# SNES-1Chip_MR_QID.net
KiCad netlist of a schematic drawn in EAGLE
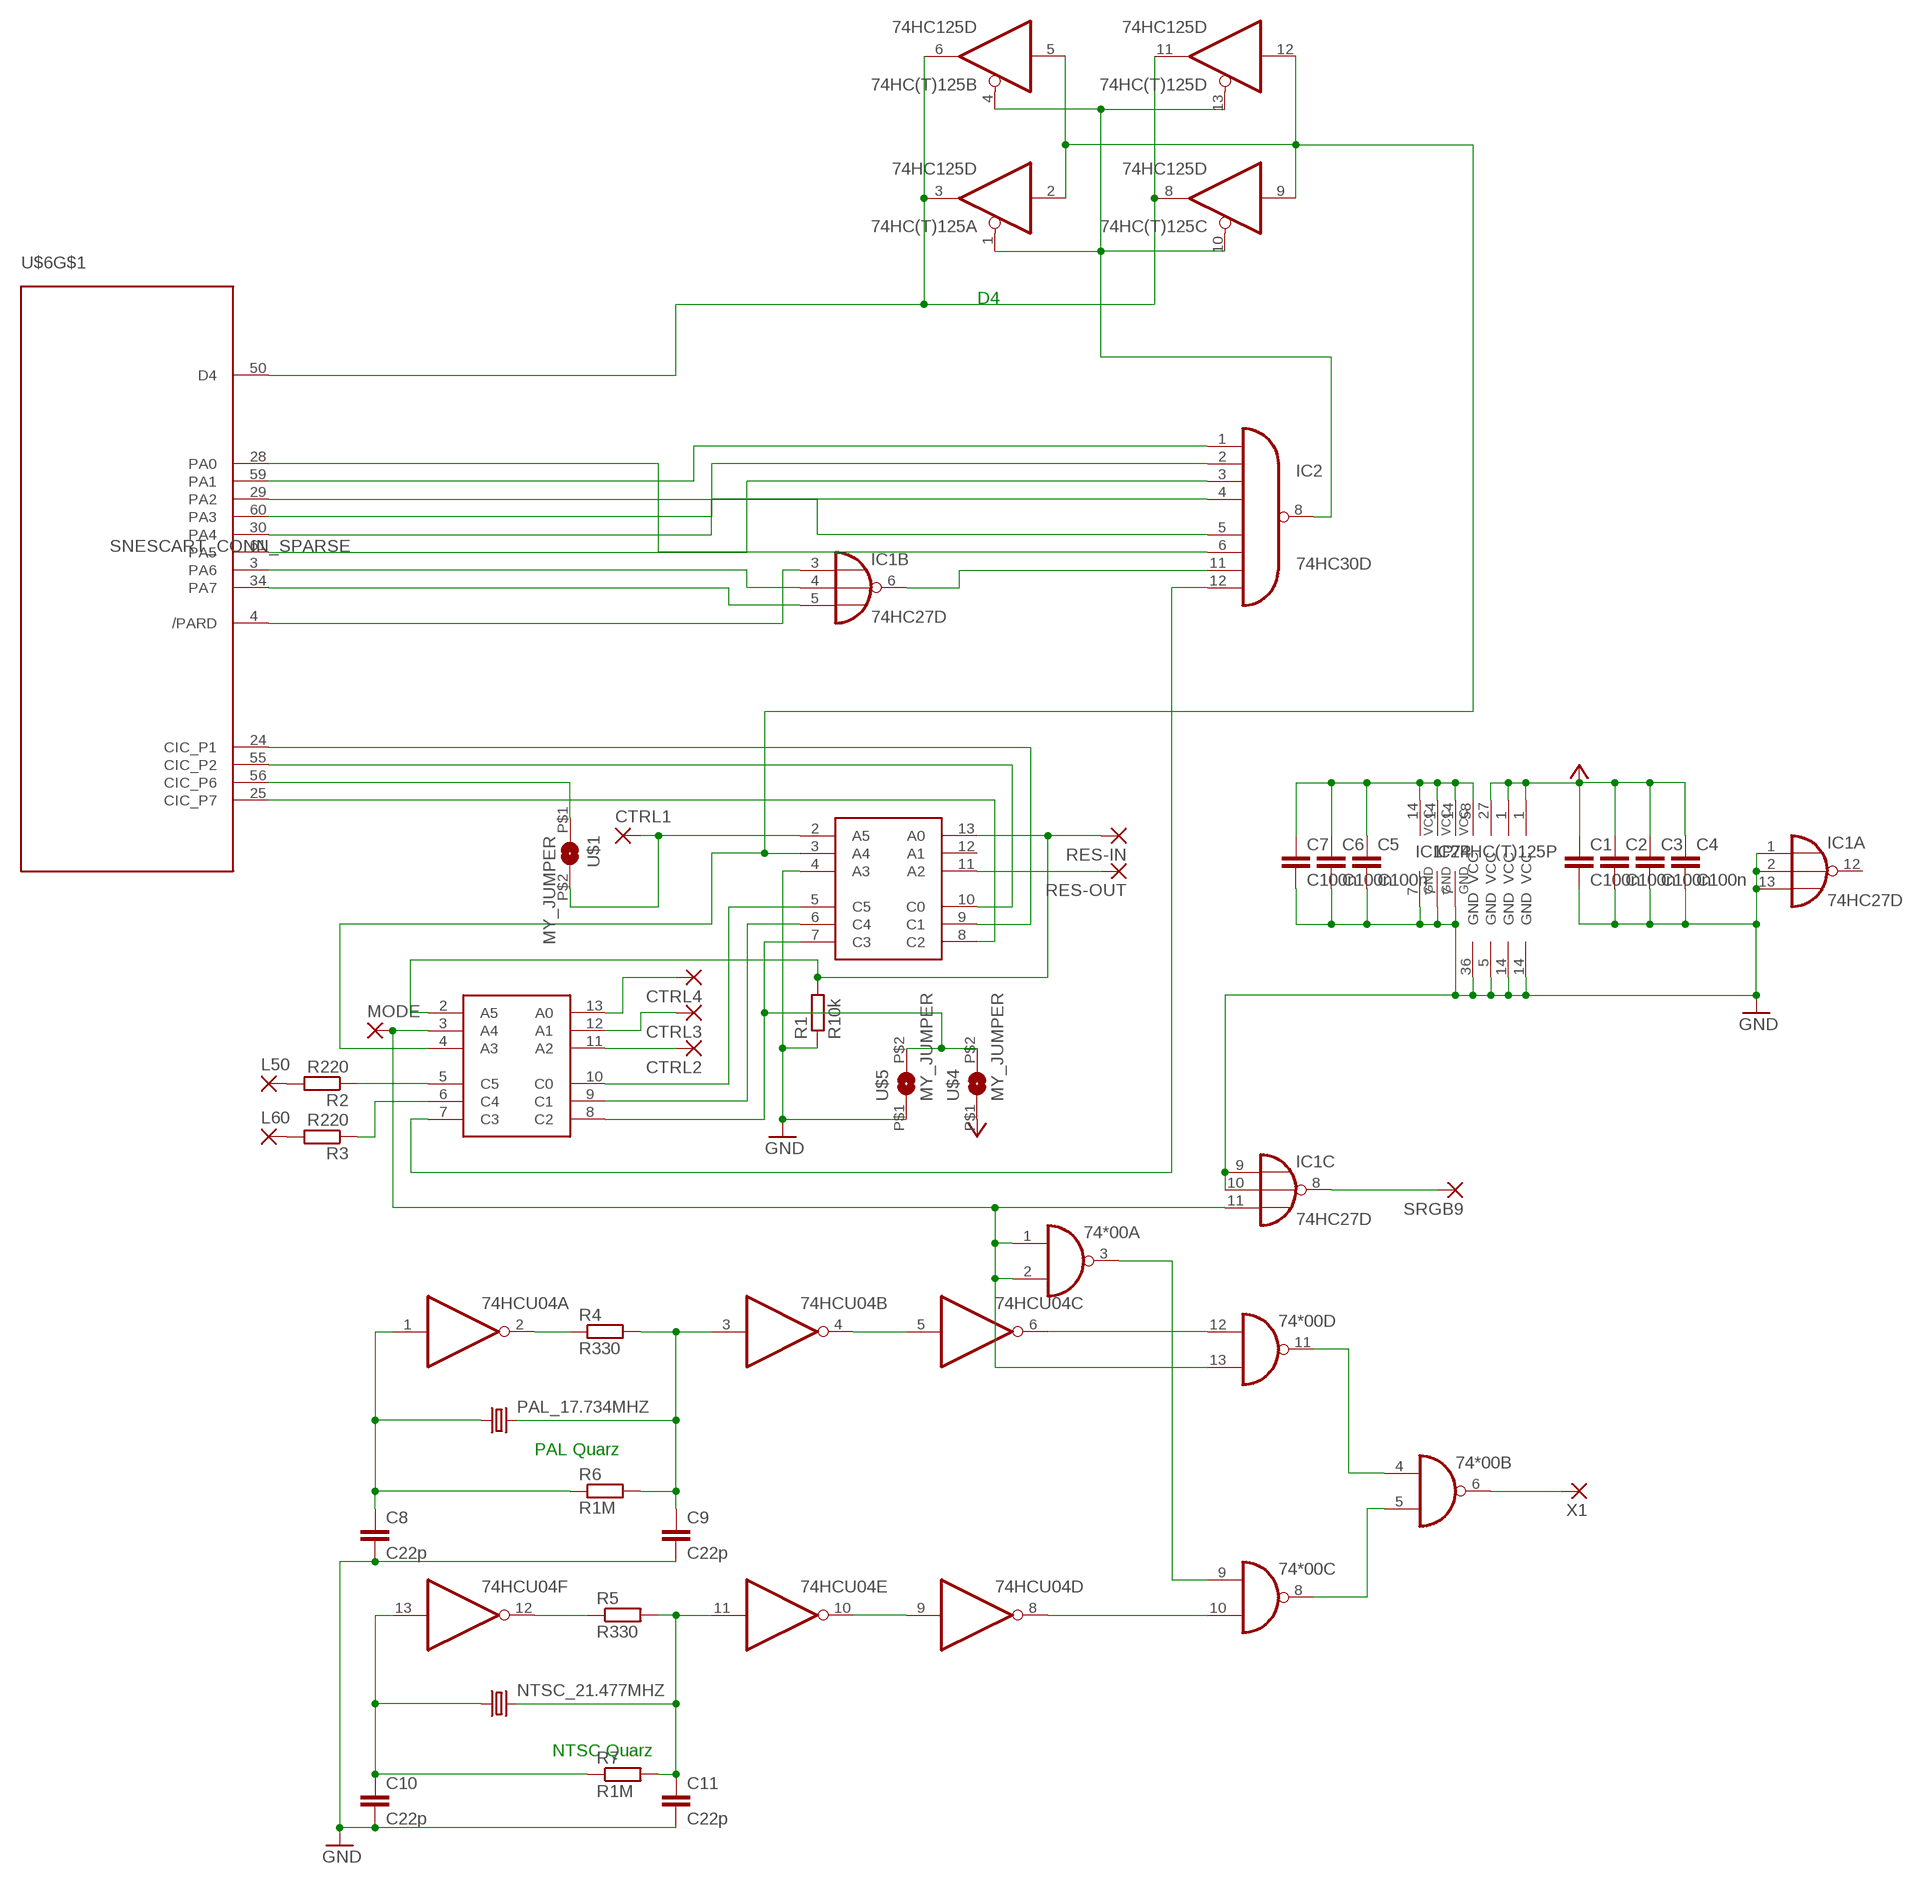
[diagram p0: schematic, sheet 1]

(export (version "E")
  (design (tool "Eeschema 10.0.6"))
  (components
    (comp (ref "74*00")
      (value "7400D")
      (footprint "eagle-import:SO14")
      (libsource (lib "eagle-import") (part "7400D"))
    )
    (comp (ref "74HC(T)125")
      (value "74HC125D")
      (footprint "eagle-import:SO14")
      (libsource (lib "eagle-import") (part "74125DHC"))
    )
    (comp (ref "74HCU04")
      (value "74HC04D")
      (footprint "eagle-import:SO14")
      (libsource (lib "eagle-import") (part "7404DHC"))
    )
    (comp (ref "C1")
      (value "C100n")
      (footprint "eagle-import:Z0805")
      (libsource (lib "eagle-import") (part "C0805"))
    )
    (comp (ref "C2")
      (value "C100n")
      (footprint "eagle-import:Z0805")
      (libsource (lib "eagle-import") (part "C0805"))
    )
    (comp (ref "C3")
      (value "C100n")
      (footprint "eagle-import:Z0805")
      (libsource (lib "eagle-import") (part "C0805"))
    )
    (comp (ref "C4")
      (value "C100n")
      (footprint "eagle-import:Z0805")
      (libsource (lib "eagle-import") (part "C0805"))
    )
    (comp (ref "C5")
      (value "C100n")
      (footprint "eagle-import:Z0805")
      (libsource (lib "eagle-import") (part "C0805"))
    )
    (comp (ref "C6")
      (value "C100n")
      (footprint "eagle-import:Z0805")
      (libsource (lib "eagle-import") (part "C0805"))
    )
    (comp (ref "C7")
      (value "C100n")
      (footprint "eagle-import:Z0805")
      (libsource (lib "eagle-import") (part "C0805"))
    )
    (comp (ref "C8")
      (value "C22p")
      (footprint "eagle-import:Z0805")
      (libsource (lib "eagle-import") (part "C0805"))
    )
    (comp (ref "C9")
      (value "C22p")
      (footprint "eagle-import:Z0805")
      (libsource (lib "eagle-import") (part "C0805"))
    )
    (comp (ref "C10")
      (value "C22p")
      (footprint "eagle-import:Z0805")
      (libsource (lib "eagle-import") (part "C0805"))
    )
    (comp (ref "C11")
      (value "C22p")
      (footprint "eagle-import:Z0805")
      (libsource (lib "eagle-import") (part "C0805"))
    )
    (comp (ref "CTRL1")
      (value "SMD2")
      (footprint "eagle-import:SMD1,27-2,54")
      (libsource (lib "eagle-import") (part "SMD2"))
    )
    (comp (ref "CTRL2")
      (value "SMD2")
      (footprint "eagle-import:SMD1,27-2,54")
      (libsource (lib "eagle-import") (part "SMD2"))
    )
    (comp (ref "CTRL3")
      (value "SMD2")
      (footprint "eagle-import:SMD1,27-2,54")
      (libsource (lib "eagle-import") (part "SMD2"))
    )
    (comp (ref "CTRL4")
      (value "SMD2")
      (footprint "eagle-import:SMD1,27-2,54")
      (libsource (lib "eagle-import") (part "SMD2"))
    )
    (comp (ref "IC1")
      (value "74HC27D")
      (footprint "eagle-import:SO14")
      (libsource (lib "eagle-import") (part "7427DHC"))
    )
    (comp (ref "IC2")
      (value "74HC30D")
      (footprint "eagle-import:SO14")
      (libsource (lib "eagle-import") (part "7430DHC"))
    )
    (comp (ref "L50")
      (value "SMD2")
      (footprint "eagle-import:SMD1,27-2,54")
      (libsource (lib "eagle-import") (part "SMD2"))
    )
    (comp (ref "L60")
      (value "SMD2")
      (footprint "eagle-import:SMD1,27-2,54")
      (libsource (lib "eagle-import") (part "SMD2"))
    )
    (comp (ref "MODE")
      (value "SMD2")
      (footprint "eagle-import:SMD1,27-2,54")
      (libsource (lib "eagle-import") (part "SMD2"))
    )
    (comp (ref "NTSC_21.477MHZ")
      (value "CRYSTALHC49UP")
      (footprint "eagle-import:HC49UP")
      (libsource (lib "eagle-import") (part "CRYSTALHC49UP"))
    )
    (comp (ref "PAL_17.734MHZ")
      (value "CRYSTALHC49UP")
      (footprint "eagle-import:HC49UP")
      (libsource (lib "eagle-import") (part "CRYSTALHC49UP"))
    )
    (comp (ref "R1")
      (value "R10k")
      (footprint "eagle-import:Z0805")
      (libsource (lib "eagle-import") (part "R0805"))
    )
    (comp (ref "R2")
      (value "R220")
      (footprint "eagle-import:Z0805")
      (libsource (lib "eagle-import") (part "R0805"))
    )
    (comp (ref "R3")
      (value "R220")
      (footprint "eagle-import:Z0805")
      (libsource (lib "eagle-import") (part "R0805"))
    )
    (comp (ref "R4")
      (value "R330")
      (footprint "eagle-import:Z0805")
      (libsource (lib "eagle-import") (part "R0805"))
    )
    (comp (ref "R5")
      (value "R330")
      (footprint "eagle-import:Z0805")
      (libsource (lib "eagle-import") (part "R0805"))
    )
    (comp (ref "R6")
      (value "R1M")
      (footprint "eagle-import:Z0805")
      (libsource (lib "eagle-import") (part "R0805"))
    )
    (comp (ref "R7")
      (value "R1M")
      (footprint "eagle-import:Z0805")
      (libsource (lib "eagle-import") (part "R0805"))
    )
    (comp (ref "RES-IN")
      (value "SMD2")
      (footprint "eagle-import:SMD1,27-2,54")
      (libsource (lib "eagle-import") (part "SMD2"))
    )
    (comp (ref "RES-OUT")
      (value "SMD2")
      (footprint "eagle-import:SMD1,27-2,54")
      (libsource (lib "eagle-import") (part "SMD2"))
    )
    (comp (ref "SRGB9")
      (value "SMD2")
      (footprint "eagle-import:SMD1,27-2,54")
      (libsource (lib "eagle-import") (part "SMD2"))
    )
    (comp (ref "U$1")
      (value "MY_JUMPER")
      (footprint "eagle-import:MYJUMP")
      (libsource (lib "eagle-import") (part "MY_JUMPER"))
    )
    (comp (ref "U$2")
      (value "PIC16F630_SIMPLE")
      (footprint "eagle-import:PIC16F630")
      (libsource (lib "eagle-import") (part "PIC16F630_SIMPLE"))
    )
    (comp (ref "U$3")
      (value "PIC16F630_SIMPLE")
      (footprint "eagle-import:PIC16F630")
      (libsource (lib "eagle-import") (part "PIC16F630_SIMPLE"))
    )
    (comp (ref "U$4")
      (value "MY_JUMPER")
      (footprint "eagle-import:MYJUMP")
      (libsource (lib "eagle-import") (part "MY_JUMPER"))
    )
    (comp (ref "U$5")
      (value "MY_JUMPER")
      (footprint "eagle-import:MYJUMP")
      (libsource (lib "eagle-import") (part "MY_JUMPER"))
    )
    (comp (ref "U$6")
      (value "SNESCART_CONN_SPARSE")
      (footprint "eagle-import:SNESCART_CONN_SPARSE")
      (libsource (lib "eagle-import") (part "SNESCART_CONN_SPARSE"))
    )
    (comp (ref "X1")
      (value "SMD2")
      (footprint "eagle-import:SMD1,27-2,54")
      (libsource (lib "eagle-import") (part "SMD2"))
    )
  )
  (nets
    (net (code "1") (name "+5V") (class "Default")
      (node (ref "C1") (pin "1") (pinfunction "1_1") (pintype "passive"))
      (node (ref "C2") (pin "1") (pinfunction "1_1") (pintype "passive"))
      (node (ref "C3") (pin "1") (pinfunction "1_1") (pintype "passive"))
      (node (ref "C4") (pin "1") (pinfunction "1_1") (pintype "passive"))
      (node (ref "U$2") (pin "1") (pinfunction "VCC_1") (pintype "bidirectional"))
      (node (ref "U$3") (pin "1") (pinfunction "VCC_1") (pintype "bidirectional"))
      (node (ref "U$4") (pin "P$1") (pinfunction "1_P$1") (pintype "passive"))
      (node (ref "U$6") (pin "27") (pinfunction "VCC_27") (pintype "bidirectional"))
    )
    (net (code "2") (name "GND") (class "Default")
      (node (ref "74HC(T)125") (pin "7") (pinfunction "GND_7") (pintype "power_in"))
      (node (ref "C1") (pin "2") (pinfunction "2_2") (pintype "passive"))
      (node (ref "C10") (pin "2") (pinfunction "2_2") (pintype "passive"))
      (node (ref "C11") (pin "2") (pinfunction "2_2") (pintype "passive"))
      (node (ref "C2") (pin "2") (pinfunction "2_2") (pintype "passive"))
      (node (ref "C3") (pin "2") (pinfunction "2_2") (pintype "passive"))
      (node (ref "C4") (pin "2") (pinfunction "2_2") (pintype "passive"))
      (node (ref "C5") (pin "2") (pinfunction "2_2") (pintype "passive"))
      (node (ref "C6") (pin "2") (pinfunction "2_2") (pintype "passive"))
      (node (ref "C7") (pin "2") (pinfunction "2_2") (pintype "passive"))
      (node (ref "C8") (pin "2") (pinfunction "2_2") (pintype "passive"))
      (node (ref "C9") (pin "2") (pinfunction "2_2") (pintype "passive"))
      (node (ref "IC1") (pin "1") (pinfunction "I0_1") (pintype "input"))
      (node (ref "IC1") (pin "10") (pinfunction "I1_10") (pintype "input"))
      (node (ref "IC1") (pin "13") (pinfunction "I2_13") (pintype "input"))
      (node (ref "IC1") (pin "2") (pinfunction "I1_2") (pintype "input"))
      (node (ref "IC1") (pin "7") (pinfunction "GND_7") (pintype "power_in"))
      (node (ref "IC1") (pin "9") (pinfunction "I0_9") (pintype "input"))
      (node (ref "IC2") (pin "7") (pinfunction "GND_7") (pintype "power_in"))
      (node (ref "R1") (pin "1") (pinfunction "1_1") (pintype "passive"))
      (node (ref "U$2") (pin "14") (pinfunction "GND_14") (pintype "bidirectional"))
      (node (ref "U$2") (pin "4") (pinfunction "A3_4") (pintype "bidirectional"))
      (node (ref "U$3") (pin "14") (pinfunction "GND_14") (pintype "bidirectional"))
      (node (ref "U$5") (pin "P$1") (pinfunction "1_P$1") (pintype "passive"))
      (node (ref "U$6") (pin "36") (pinfunction "GND_36") (pintype "bidirectional"))
      (node (ref "U$6") (pin "5") (pinfunction "GND_5") (pintype "bidirectional"))
    )
    (net (code "3") (name "Net-(74*00A-I0)") (class "Default")
      (node (ref "74*00") (pin "1") (pinfunction "I0_1") (pintype "input"))
      (node (ref "74*00") (pin "13") (pinfunction "I1_13") (pintype "input"))
      (node (ref "74*00") (pin "2") (pinfunction "I1_2") (pintype "input"))
      (node (ref "IC1") (pin "11") (pinfunction "I2_11") (pintype "input"))
      (node (ref "MODE") (pin "1") (pinfunction "P_1") (pintype "passive"))
      (node (ref "U$3") (pin "3") (pinfunction "A4_3") (pintype "bidirectional"))
    )
    (net (code "4") (name "Net-(74*00A-O)") (class "Default")
      (node (ref "74*00") (pin "3") (pinfunction "O_3") (pintype "output"))
      (node (ref "74*00") (pin "9") (pinfunction "I0_9") (pintype "input"))
    )
    (net (code "5") (name "Net-(74*00B-I0)") (class "Default")
      (node (ref "74*00") (pin "11") (pinfunction "O_11") (pintype "output"))
      (node (ref "74*00") (pin "4") (pinfunction "I0_4") (pintype "input"))
    )
    (net (code "6") (name "Net-(74*00B-I1)") (class "Default")
      (node (ref "74*00") (pin "5") (pinfunction "I1_5") (pintype "input"))
      (node (ref "74*00") (pin "8") (pinfunction "O_8") (pintype "output"))
    )
    (net (code "7") (name "Net-(74*00B-O)") (class "Default")
      (node (ref "74*00") (pin "6") (pinfunction "O_6") (pintype "output"))
      (node (ref "X1") (pin "1") (pinfunction "P_1") (pintype "passive"))
    )
    (net (code "8") (name "Net-(74*00C-I1)") (class "Default")
      (node (ref "74*00") (pin "10") (pinfunction "I1_10") (pintype "input"))
      (node (ref "74HCU04") (pin "8") (pinfunction "O_8") (pintype "output"))
    )
    (net (code "9") (name "Net-(74*00D-I0)") (class "Default")
      (node (ref "74*00") (pin "12") (pinfunction "I0_12") (pintype "input"))
      (node (ref "74HCU04") (pin "6") (pinfunction "O_6") (pintype "output"))
    )
    (net (code "10") (name "Net-(74HC(T)125A-I)") (class "Default")
      (node (ref "74HC(T)125") (pin "12") (pinfunction "I_12") (pintype "input"))
      (node (ref "74HC(T)125") (pin "2") (pinfunction "I_2") (pintype "input"))
      (node (ref "74HC(T)125") (pin "5") (pinfunction "I_5") (pintype "input"))
      (node (ref "74HC(T)125") (pin "9") (pinfunction "I_9") (pintype "input"))
      (node (ref "U$2") (pin "3") (pinfunction "A4_3") (pintype "bidirectional"))
      (node (ref "U$3") (pin "4") (pinfunction "A3_4") (pintype "bidirectional"))
    )
    (net (code "11") (name "Net-(74HC(T)125A-O)") (class "Default")
      (node (ref "74HC(T)125") (pin "11") (pinfunction "O_11") (pintype "tri_state"))
      (node (ref "74HC(T)125") (pin "3") (pinfunction "O_3") (pintype "tri_state"))
      (node (ref "74HC(T)125") (pin "6") (pinfunction "O_6") (pintype "tri_state"))
      (node (ref "74HC(T)125") (pin "8") (pinfunction "O_8") (pintype "tri_state"))
      (node (ref "U$6") (pin "50") (pinfunction "D4_50") (pintype "bidirectional"))
    )
    (net (code "12") (name "Net-(74HC(T)125A-OE)") (class "Default")
      (node (ref "74HC(T)125") (pin "1") (pinfunction "OE_1") (pintype "input"))
      (node (ref "74HC(T)125") (pin "10") (pinfunction "OE_10") (pintype "input"))
      (node (ref "74HC(T)125") (pin "13") (pinfunction "OE_13") (pintype "input"))
      (node (ref "74HC(T)125") (pin "4") (pinfunction "OE_4") (pintype "input"))
      (node (ref "IC2") (pin "8") (pinfunction "O_8") (pintype "output"))
    )
    (net (code "13") (name "Net-(74HC(T)125E-VCC)") (class "Default")
      (node (ref "74HC(T)125") (pin "14") (pinfunction "VCC_14") (pintype "power_in"))
      (node (ref "C5") (pin "1") (pinfunction "1_1") (pintype "passive"))
      (node (ref "C6") (pin "1") (pinfunction "1_1") (pintype "passive"))
      (node (ref "C7") (pin "1") (pinfunction "1_1") (pintype "passive"))
      (node (ref "IC1") (pin "14") (pinfunction "VCC_14") (pintype "power_in"))
      (node (ref "IC2") (pin "14") (pinfunction "VCC_14") (pintype "power_in"))
      (node (ref "U$6") (pin "58") (pinfunction "VCC_58") (pintype "bidirectional"))
    )
    (net (code "14") (name "Net-(74HCU04A-I)") (class "Default")
      (node (ref "74HCU04") (pin "1") (pinfunction "I_1") (pintype "input"))
      (node (ref "C8") (pin "1") (pinfunction "1_1") (pintype "passive"))
      (node (ref "PAL_17.734MHZ") (pin "1") (pinfunction "1_1") (pintype "passive"))
      (node (ref "R6") (pin "1") (pinfunction "1_1") (pintype "passive"))
    )
    (net (code "15") (name "Net-(74HCU04A-O)") (class "Default")
      (node (ref "74HCU04") (pin "2") (pinfunction "O_2") (pintype "output"))
      (node (ref "R4") (pin "1") (pinfunction "1_1") (pintype "passive"))
    )
    (net (code "16") (name "Net-(74HCU04B-I)") (class "Default")
      (node (ref "74HCU04") (pin "3") (pinfunction "I_3") (pintype "input"))
      (node (ref "C9") (pin "1") (pinfunction "1_1") (pintype "passive"))
      (node (ref "PAL_17.734MHZ") (pin "2") (pinfunction "2_2") (pintype "passive"))
      (node (ref "R4") (pin "2") (pinfunction "2_2") (pintype "passive"))
      (node (ref "R6") (pin "2") (pinfunction "2_2") (pintype "passive"))
    )
    (net (code "17") (name "Net-(74HCU04B-O)") (class "Default")
      (node (ref "74HCU04") (pin "4") (pinfunction "O_4") (pintype "output"))
      (node (ref "74HCU04") (pin "5") (pinfunction "I_5") (pintype "input"))
    )
    (net (code "18") (name "Net-(74HCU04D-I)") (class "Default")
      (node (ref "74HCU04") (pin "10") (pinfunction "O_10") (pintype "output"))
      (node (ref "74HCU04") (pin "9") (pinfunction "I_9") (pintype "input"))
    )
    (net (code "19") (name "Net-(74HCU04E-I)") (class "Default")
      (node (ref "74HCU04") (pin "11") (pinfunction "I_11") (pintype "input"))
      (node (ref "C11") (pin "1") (pinfunction "1_1") (pintype "passive"))
      (node (ref "NTSC_21.477MHZ") (pin "2") (pinfunction "2_2") (pintype "passive"))
      (node (ref "R5") (pin "2") (pinfunction "2_2") (pintype "passive"))
      (node (ref "R7") (pin "2") (pinfunction "2_2") (pintype "passive"))
    )
    (net (code "20") (name "Net-(74HCU04F-I)") (class "Default")
      (node (ref "74HCU04") (pin "13") (pinfunction "I_13") (pintype "input"))
      (node (ref "C10") (pin "1") (pinfunction "1_1") (pintype "passive"))
      (node (ref "NTSC_21.477MHZ") (pin "1") (pinfunction "1_1") (pintype "passive"))
      (node (ref "R7") (pin "1") (pinfunction "1_1") (pintype "passive"))
    )
    (net (code "21") (name "Net-(74HCU04F-O)") (class "Default")
      (node (ref "74HCU04") (pin "12") (pinfunction "O_12") (pintype "output"))
      (node (ref "R5") (pin "1") (pinfunction "1_1") (pintype "passive"))
    )
    (net (code "22") (name "Net-(CTRL1-P)") (class "Default")
      (node (ref "CTRL1") (pin "1") (pinfunction "P_1") (pintype "passive"))
      (node (ref "U$1") (pin "P$2") (pinfunction "2_P$2") (pintype "passive"))
      (node (ref "U$2") (pin "2") (pinfunction "A5_2") (pintype "bidirectional"))
    )
    (net (code "23") (name "Net-(CTRL2-P)") (class "Default")
      (node (ref "CTRL2") (pin "1") (pinfunction "P_1") (pintype "passive"))
      (node (ref "U$3") (pin "11") (pinfunction "A2_11") (pintype "bidirectional"))
    )
    (net (code "24") (name "Net-(CTRL3-P)") (class "Default")
      (node (ref "CTRL3") (pin "1") (pinfunction "P_1") (pintype "passive"))
      (node (ref "U$3") (pin "12") (pinfunction "A1_12") (pintype "bidirectional"))
    )
    (net (code "25") (name "Net-(CTRL4-P)") (class "Default")
      (node (ref "CTRL4") (pin "1") (pinfunction "P_1") (pintype "passive"))
      (node (ref "U$3") (pin "13") (pinfunction "A0_13") (pintype "bidirectional"))
    )
    (net (code "26") (name "Net-(IC1B-I0)") (class "Default")
      (node (ref "IC1") (pin "3") (pinfunction "I0_3") (pintype "input"))
      (node (ref "U$6") (pin "4") (pinfunction "/PARD_4") (pintype "bidirectional"))
    )
    (net (code "27") (name "Net-(IC1B-I1)") (class "Default")
      (node (ref "IC1") (pin "4") (pinfunction "I1_4") (pintype "input"))
      (node (ref "U$6") (pin "3") (pinfunction "PA6_3") (pintype "bidirectional"))
    )
    (net (code "28") (name "Net-(IC1B-I2)") (class "Default")
      (node (ref "IC1") (pin "5") (pinfunction "I2_5") (pintype "input"))
      (node (ref "U$6") (pin "34") (pinfunction "PA7_34") (pintype "bidirectional"))
    )
    (net (code "29") (name "Net-(IC1B-O)") (class "Default")
      (node (ref "IC1") (pin "6") (pinfunction "O_6") (pintype "output"))
      (node (ref "IC2") (pin "11") (pinfunction "I6_11") (pintype "input"))
    )
    (net (code "30") (name "Net-(IC1C-O)") (class "Default")
      (node (ref "IC1") (pin "8") (pinfunction "O_8") (pintype "output"))
      (node (ref "SRGB9") (pin "1") (pinfunction "P_1") (pintype "passive"))
    )
    (net (code "31") (name "Net-(IC2A-I0)") (class "Default")
      (node (ref "IC2") (pin "1") (pinfunction "I0_1") (pintype "input"))
      (node (ref "U$6") (pin "59") (pinfunction "PA1_59") (pintype "bidirectional"))
    )
    (net (code "32") (name "Net-(IC2A-I1)") (class "Default")
      (node (ref "IC2") (pin "2") (pinfunction "I1_2") (pintype "input"))
      (node (ref "U$6") (pin "60") (pinfunction "PA3_60") (pintype "bidirectional"))
    )
    (net (code "33") (name "Net-(IC2A-I2)") (class "Default")
      (node (ref "IC2") (pin "3") (pinfunction "I2_3") (pintype "input"))
      (node (ref "U$6") (pin "61") (pinfunction "PA5_61") (pintype "bidirectional"))
    )
    (net (code "34") (name "Net-(IC2A-I3)") (class "Default")
      (node (ref "IC2") (pin "4") (pinfunction "I3_4") (pintype "input"))
      (node (ref "U$6") (pin "30") (pinfunction "PA4_30") (pintype "bidirectional"))
    )
    (net (code "35") (name "Net-(IC2A-I4)") (class "Default")
      (node (ref "IC2") (pin "5") (pinfunction "I4_5") (pintype "input"))
      (node (ref "U$6") (pin "29") (pinfunction "PA2_29") (pintype "bidirectional"))
    )
    (net (code "36") (name "Net-(IC2A-I5)") (class "Default")
      (node (ref "IC2") (pin "6") (pinfunction "I5_6") (pintype "input"))
      (node (ref "U$6") (pin "28") (pinfunction "PA0_28") (pintype "bidirectional"))
    )
    (net (code "37") (name "Net-(IC2A-I7)") (class "Default")
      (node (ref "IC2") (pin "12") (pinfunction "I7_12") (pintype "input"))
      (node (ref "U$3") (pin "7") (pinfunction "C3_7") (pintype "bidirectional"))
    )
    (net (code "38") (name "Net-(L50-P)") (class "Default")
      (node (ref "L50") (pin "1") (pinfunction "P_1") (pintype "passive"))
      (node (ref "R2") (pin "2") (pinfunction "2_2") (pintype "passive"))
    )
    (net (code "39") (name "Net-(L60-P)") (class "Default")
      (node (ref "L60") (pin "1") (pinfunction "P_1") (pintype "passive"))
      (node (ref "R3") (pin "2") (pinfunction "2_2") (pintype "passive"))
    )
    (net (code "40") (name "Net-(RES-IN-P)") (class "Default")
      (node (ref "R1") (pin "2") (pinfunction "2_2") (pintype "passive"))
      (node (ref "RES-IN") (pin "1") (pinfunction "P_1") (pintype "passive"))
      (node (ref "U$2") (pin "13") (pinfunction "A0_13") (pintype "bidirectional"))
      (node (ref "U$3") (pin "2") (pinfunction "A5_2") (pintype "bidirectional"))
    )
    (net (code "41") (name "Net-(RES-OUT-P)") (class "Default")
      (node (ref "RES-OUT") (pin "1") (pinfunction "P_1") (pintype "passive"))
      (node (ref "U$2") (pin "11") (pinfunction "A2_11") (pintype "bidirectional"))
    )
    (net (code "42") (name "Net-(U$1-1)") (class "Default")
      (node (ref "U$1") (pin "P$1") (pinfunction "1_P$1") (pintype "passive"))
      (node (ref "U$6") (pin "56") (pinfunction "CIC_P6_56") (pintype "bidirectional"))
    )
    (net (code "43") (name "Net-(U$2A-C0)") (class "Default")
      (node (ref "U$2") (pin "10") (pinfunction "C0_10") (pintype "bidirectional"))
      (node (ref "U$6") (pin "55") (pinfunction "CIC_P2_55") (pintype "bidirectional"))
    )
    (net (code "44") (name "Net-(U$2A-C1)") (class "Default")
      (node (ref "U$2") (pin "9") (pinfunction "C1_9") (pintype "bidirectional"))
      (node (ref "U$6") (pin "24") (pinfunction "CIC_P1_24") (pintype "bidirectional"))
    )
    (net (code "45") (name "Net-(U$2A-C2)") (class "Default")
      (node (ref "U$2") (pin "8") (pinfunction "C2_8") (pintype "bidirectional"))
      (node (ref "U$6") (pin "25") (pinfunction "CIC_P7_25") (pintype "bidirectional"))
    )
    (net (code "46") (name "Net-(U$2A-C3)") (class "Default")
      (node (ref "U$2") (pin "7") (pinfunction "C3_7") (pintype "bidirectional"))
      (node (ref "U$3") (pin "8") (pinfunction "C2_8") (pintype "bidirectional"))
      (node (ref "U$4") (pin "P$2") (pinfunction "2_P$2") (pintype "passive"))
      (node (ref "U$5") (pin "P$2") (pinfunction "2_P$2") (pintype "passive"))
    )
    (net (code "47") (name "Net-(U$2A-C4)") (class "Default")
      (node (ref "U$2") (pin "6") (pinfunction "C4_6") (pintype "bidirectional"))
      (node (ref "U$3") (pin "9") (pinfunction "C1_9") (pintype "bidirectional"))
    )
    (net (code "48") (name "Net-(U$2A-C5)") (class "Default")
      (node (ref "U$2") (pin "5") (pinfunction "C5_5") (pintype "bidirectional"))
      (node (ref "U$3") (pin "10") (pinfunction "C0_10") (pintype "bidirectional"))
    )
    (net (code "49") (name "Net-(U$3A-C4)") (class "Default")
      (node (ref "R3") (pin "1") (pinfunction "1_1") (pintype "passive"))
      (node (ref "U$3") (pin "6") (pinfunction "C4_6") (pintype "bidirectional"))
    )
    (net (code "50") (name "Net-(U$3A-C5)") (class "Default")
      (node (ref "R2") (pin "1") (pinfunction "1_1") (pintype "passive"))
      (node (ref "U$3") (pin "5") (pinfunction "C5_5") (pintype "bidirectional"))
    )
    (net (code "51") (name "unconnected-(IC1A-O-Pad12)") (class "Default")
      (node (ref "IC1") (pin "12") (pinfunction "O_12") (pintype "output"))
    )
    (net (code "52") (name "unconnected-(U$2A-A1-Pad12)") (class "Default")
      (node (ref "U$2") (pin "12") (pinfunction "A1_12") (pintype "bidirectional"))
    )
  )
)
